# 1-Holberton_Child_Top.net
KiCad netlist of a schematic drawn in Altium Designer
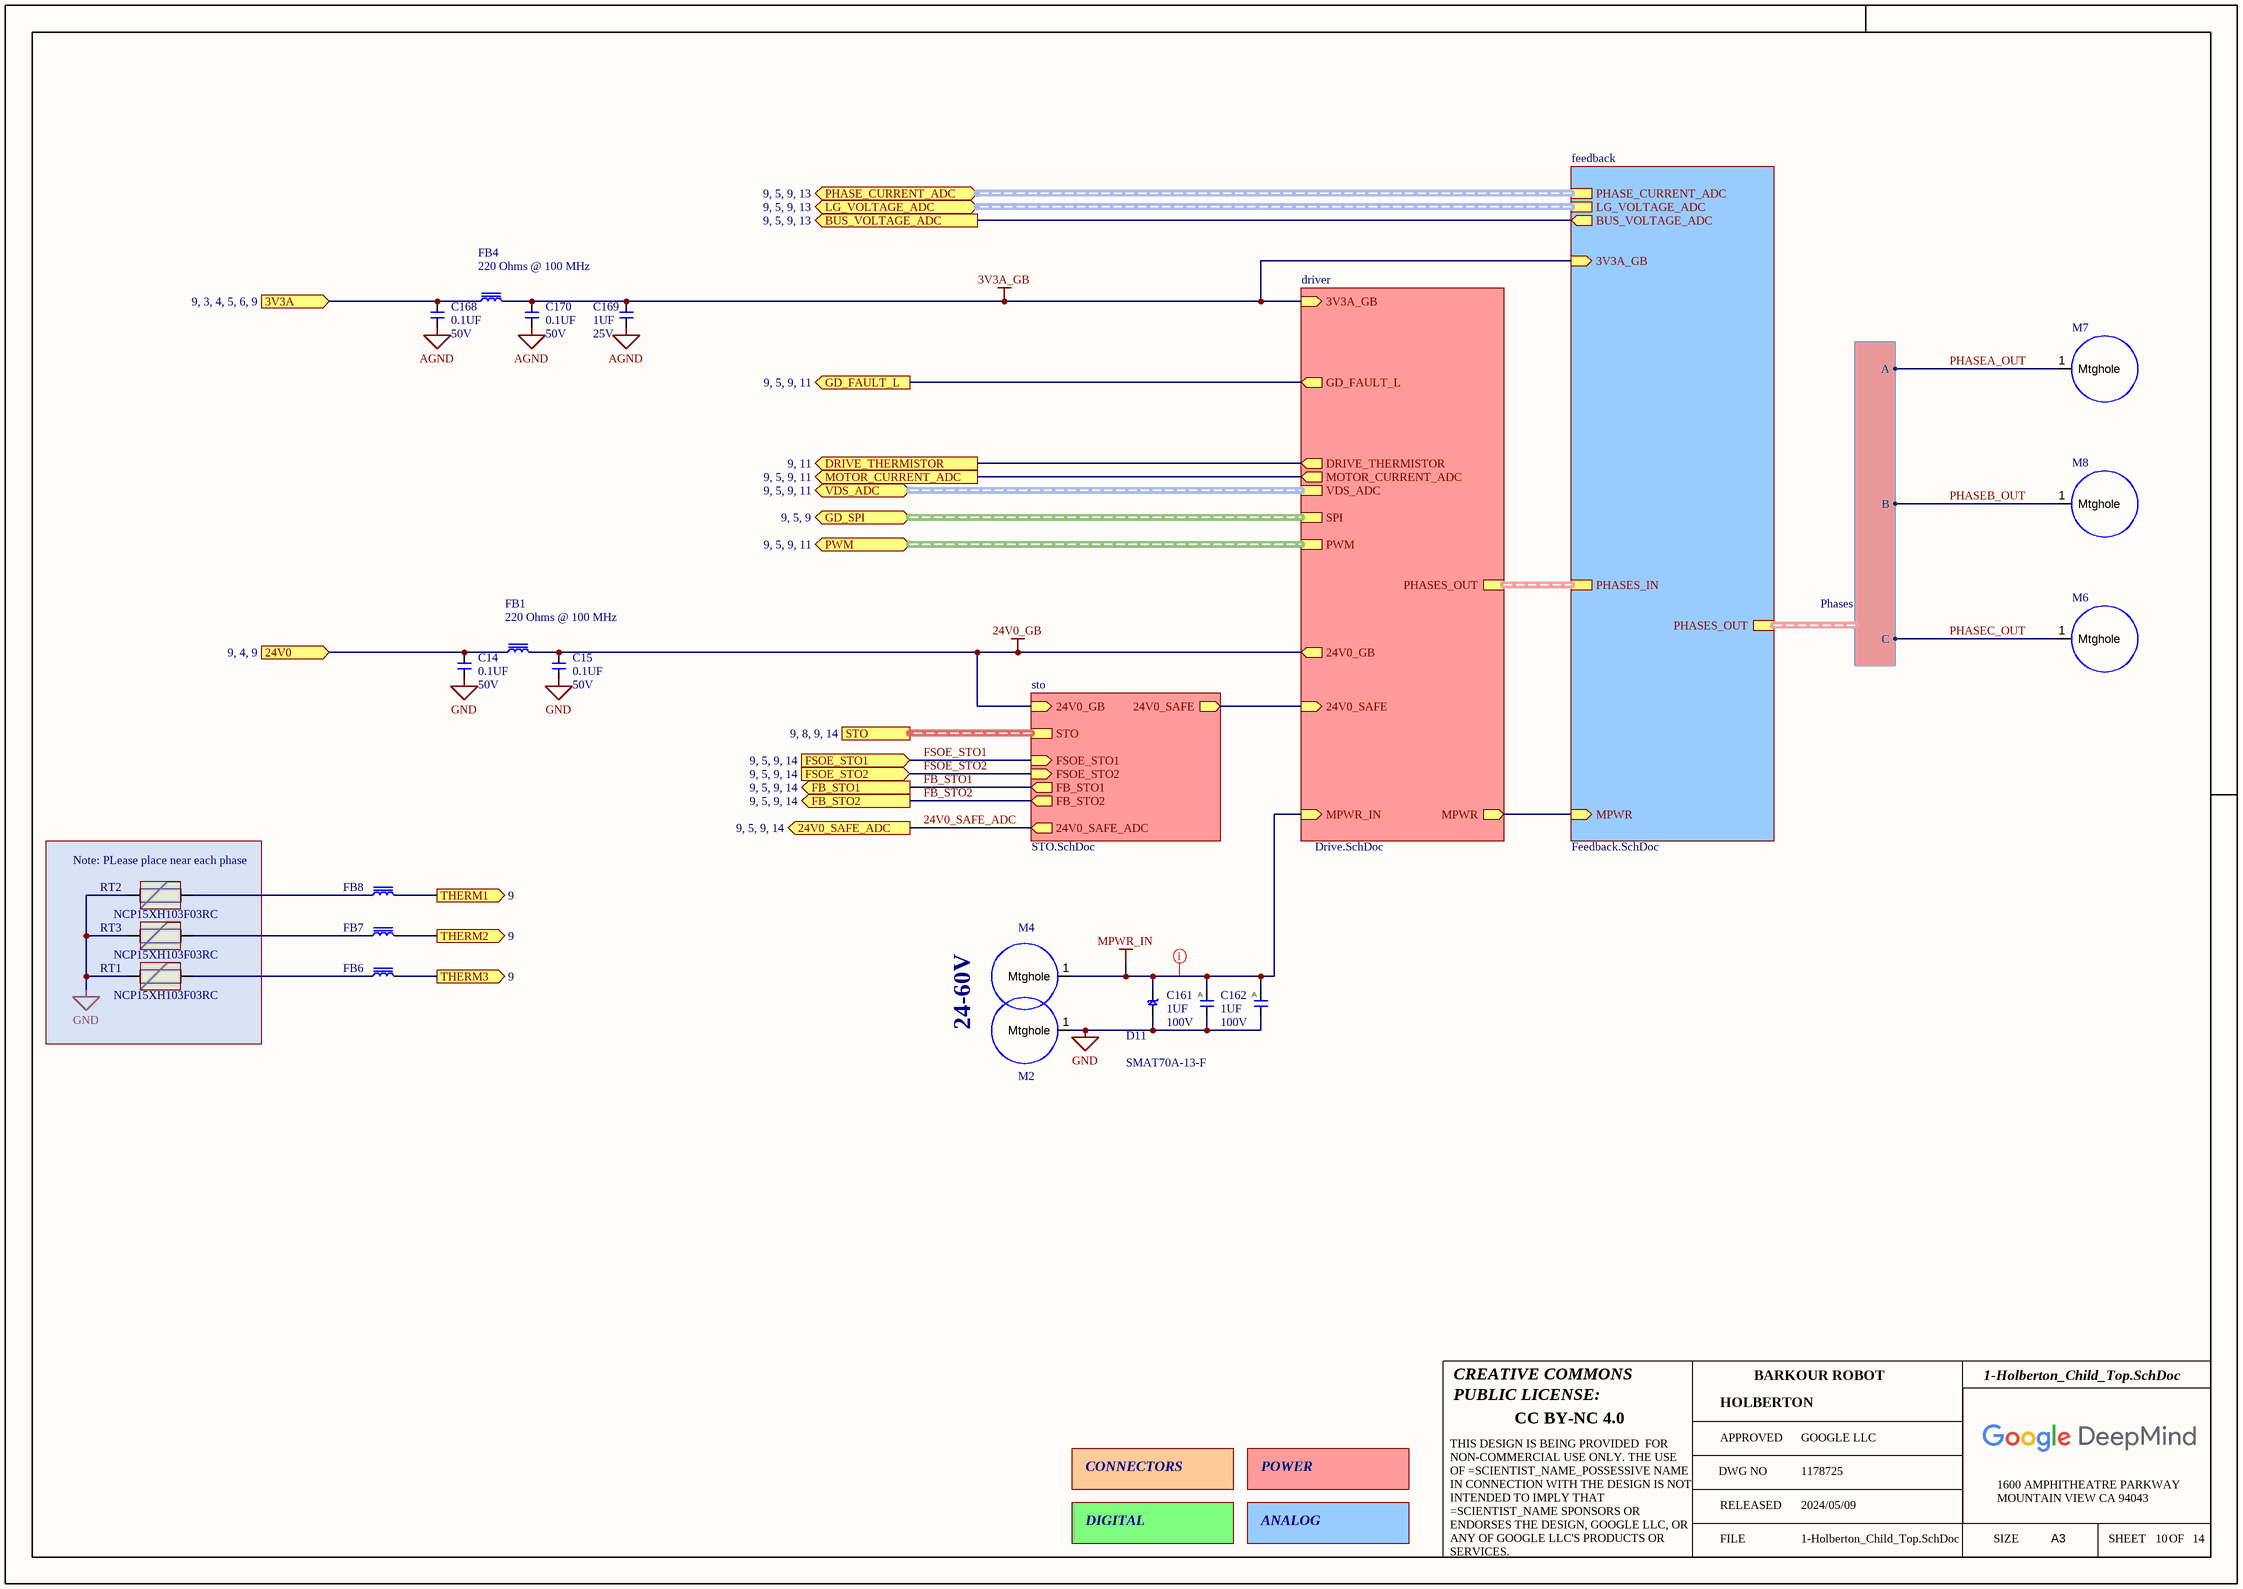
[diagram p0: 1-Holberton_Child_Top.SchDoc]

(export (version "E")
  (design (tool "Eeschema 10.0.6"))
  (components
    (comp (ref "C14")
      (value "0.1UF")
      (footprint "C0402")
      (description "CAP, CER, X5R, 0.1uF, 10%, 50V, 0402, 0.55mm")
      (fields
        (field (name "MFG") "YAGEO")
        (field (name "VOLTAGE") "50V")
        (field (name "Comment") "__Template_Cap")
      )
      (libsource (lib "AltiumReleaseLibDB") (part "__Template_Cap"))
    )
    (comp (ref "C15")
      (value "0.1UF")
      (footprint "C0402")
      (description "CAP, CER, X5R, 0.1uF, 10%, 50V, 0402, 0.55mm")
      (fields
        (field (name "MFG") "YAGEO")
        (field (name "VOLTAGE") "50V")
        (field (name "Comment") "__Template_Cap")
      )
      (libsource (lib "AltiumReleaseLibDB") (part "__Template_Cap"))
    )
    (comp (ref "C161")
      (value "1UF")
      (footprint "C0805")
      (description "CAP, CER, X7S, 1uF, 20%, 100V, 0805")
      (fields
        (field (name "MFG") "TDK")
        (field (name "VOLTAGE") "100V")
        (field (name "Comment") "__Template_Cap_Auto")
      )
      (libsource (lib "AltiumReleaseLibDB") (part "__Template_Cap_Auto"))
    )
    (comp (ref "C162")
      (value "1UF")
      (footprint "C0805")
      (description "CAP, CER, X7S, 1uF, 20%, 100V, 0805")
      (fields
        (field (name "MFG") "TDK")
        (field (name "VOLTAGE") "100V")
        (field (name "Comment") "__Template_Cap_Auto")
      )
      (libsource (lib "AltiumReleaseLibDB") (part "__Template_Cap_Auto"))
    )
    (comp (ref "C168")
      (value "0.1UF")
      (footprint "C0402")
      (description "CAP, CER, X5R, 0.1uF, 10%, 50V, 0402, 0.55mm")
      (fields
        (field (name "MFG") "YAGEO")
        (field (name "VOLTAGE") "50V")
        (field (name "Comment") "__Template_Cap")
      )
      (libsource (lib "AltiumReleaseLibDB") (part "__Template_Cap"))
    )
    (comp (ref "C169")
      (value "1UF")
      (footprint "C0402")
      (description "CAP, CER, X5R, 1uF, 10%, 25V, 0402")
      (fields
        (field (name "MFG") "TDK")
        (field (name "VOLTAGE") "25V")
        (field (name "Comment") "__Template_Cap")
      )
      (libsource (lib "AltiumReleaseLibDB") (part "__Template_Cap"))
    )
    (comp (ref "C170")
      (value "0.1UF")
      (footprint "C0402")
      (description "CAP, CER, X5R, 0.1uF, 10%, 50V, 0402, 0.55mm")
      (fields
        (field (name "MFG") "YAGEO")
        (field (name "VOLTAGE") "50V")
        (field (name "Comment") "__Template_Cap")
      )
      (libsource (lib "AltiumReleaseLibDB") (part "__Template_Cap"))
    )
    (comp (ref "D11")
      (value "SMAT70A-13-F")
      (footprint "SMA_B130-13-F")
      (description "DIODE, TVS, UNI-DIR, 70VR, 100VCL, 400W, 140PF @1MHZ, SMA")
      (fields (field (name "MFG") "Diodes Incorporated") (field (name "Comment") "__Template_Diode_TVS_A/K"))
      (libsource (lib "AltiumReleaseLibDB") (part "__Template_Diode_TVS_A/K"))
    )
    (comp (ref "FB1")
      (value "220 Ohms @ 100 MHz")
      (footprint "INDC160X80X105L30N")
      (description "FERRITE BEAD 220 OHM 0603 1LN")
      (fields
        (field (name "MFG") "Laird-Signal Integrity Products")
        (field (name "Comment") "LAIRD MI0603L221R-10")
      )
      (libsource (lib "Components") (part "FB"))
    )
    (comp (ref "FB4")
      (value "220 Ohms @ 100 MHz")
      (footprint "INDC160X80X105L30N")
      (description "FERRITE BEAD 220 OHM 0603 1LN")
      (fields
        (field (name "MFG") "Laird-Signal Integrity Products")
        (field (name "Comment") "LAIRD MI0603L221R-10")
      )
      (libsource (lib "Components") (part "FB"))
    )
    (comp (ref "FB6")
      (value "LAIRD MI0603L221R-10")
      (footprint "INDC160X80X105L30N")
      (description "FERRITE BEAD 220 OHM 0603 1LN")
      (fields (field (name "MFG") "Laird-Signal Integrity Products"))
      (libsource (lib "Components") (part "FB"))
    )
    (comp (ref "FB7")
      (value "LAIRD MI0603L221R-10")
      (footprint "INDC160X80X105L30N")
      (description "FERRITE BEAD 220 OHM 0603 1LN")
      (fields (field (name "MFG") "Laird-Signal Integrity Products"))
      (libsource (lib "Components") (part "FB"))
    )
    (comp (ref "FB8")
      (value "LAIRD MI0603L221R-10")
      (footprint "INDC160X80X105L30N")
      (description "FERRITE BEAD 220 OHM 0603 1LN")
      (fields (field (name "MFG") "Laird-Signal Integrity Products"))
      (libsource (lib "Components") (part "FB"))
    )
    (comp (ref "M2")
      (value "1.7mm hole 5mm pad")
      (footprint "1.7hole5padRD")
      (libsource (lib "MiscSch1") (part "MtgHole_1"))
    )
    (comp (ref "M4")
      (value "1.7mm hole 5mm pad")
      (footprint "1.7hole5padRD")
      (libsource (lib "MiscSch1") (part "MtgHole_1"))
    )
    (comp (ref "M6")
      (value "Keystone_8737")
      (footprint "Keystone_8737")
      (description "Motor lead attachement points Keystone_8737")
      (fields (field (name "MFG") "Keystone Electronics"))
      (libsource (lib "MiscSch1") (part "MtgHole_1"))
    )
    (comp (ref "M7")
      (value "Keystone_8737")
      (footprint "Keystone_8737")
      (description "Motor lead attachement points Keystone_8737")
      (fields (field (name "MFG") "Keystone Electronics"))
      (libsource (lib "MiscSch1") (part "MtgHole_1"))
    )
    (comp (ref "M8")
      (value "Keystone_8737")
      (footprint "Keystone_8737")
      (description "Motor lead attachement points Keystone_8737")
      (fields (field (name "MFG") "Keystone Electronics"))
      (libsource (lib "MiscSch1") (part "MtgHole_1"))
    )
    (comp (ref "RT1")
      (value "__Template_Thermistor")
      (footprint "R0402")
      (description "SENSOR, THERMISTOR, NTC, 10K, 1%, 3380K, 100mW, 0402")
      (fields (field (name "MFG") "Murata Electronics") (field (name "MFG P/N") "NCP15XH103F03RC"))
      (libsource (lib "AltiumReleaseLibDB") (part "__Template_Thermistor"))
    )
    (comp (ref "RT2")
      (value "__Template_Thermistor")
      (footprint "R0402")
      (description "SENSOR, THERMISTOR, NTC, 10K, 1%, 3380K, 100mW, 0402")
      (fields (field (name "MFG") "Murata Electronics") (field (name "MFG P/N") "NCP15XH103F03RC"))
      (libsource (lib "AltiumReleaseLibDB") (part "__Template_Thermistor"))
    )
    (comp (ref "RT3")
      (value "__Template_Thermistor")
      (footprint "R0402")
      (description "SENSOR, THERMISTOR, NTC, 10K, 1%, 3380K, 100mW, 0402")
      (fields (field (name "MFG") "Murata Electronics") (field (name "MFG P/N") "NCP15XH103F03RC"))
      (libsource (lib "AltiumReleaseLibDB") (part "__Template_Thermistor"))
    )
  )
  (nets
    (net (code "3") (name "/3V3A") (class "Default")
      (node (ref "C168") (pin "1") (pintype "passive"))
      (node (ref "FB4") (pin "1") (pintype "passive"))
    )
    (net (code "4") (name "/24V0") (class "Default")
      (node (ref "C14") (pin "1") (pintype "passive"))
      (node (ref "FB1") (pin "1") (pintype "passive"))
    )
    (net (code "18") (name "/PHASEA_OUT") (class "Default")
      (node (ref "M7") (pin "1") (pinfunction "Mtghole_1") (pintype "passive"))
    )
    (net (code "19") (name "/PHASEB_OUT") (class "Default")
      (node (ref "M8") (pin "1") (pinfunction "Mtghole_1") (pintype "passive"))
    )
    (net (code "20") (name "/PHASEC_OUT") (class "Default")
      (node (ref "M6") (pin "1") (pinfunction "Mtghole_1") (pintype "passive"))
    )
    (net (code "25") (name "/THERM1") (class "Default") (node (ref "FB8") (pin "2") (pintype "passive")))
    (net (code "26") (name "/THERM2") (class "Default") (node (ref "FB7") (pin "2") (pintype "passive")))
    (net (code "27") (name "/THERM3") (class "Default") (node (ref "FB6") (pin "2") (pintype "passive")))
    (net (code "30") (name "3V3A_GB") (class "Default")
      (node (ref "C169") (pin "1") (pintype "passive"))
      (node (ref "C170") (pin "1") (pintype "passive"))
      (node (ref "FB4") (pin "2") (pintype "passive"))
    )
    (net (code "31") (name "24V0_GB") (class "Default")
      (node (ref "C15") (pin "1") (pintype "passive"))
      (node (ref "FB1") (pin "2") (pintype "passive"))
    )
    (net (code "32") (name "AGND") (class "Default")
      (node (ref "C168") (pin "2") (pintype "passive"))
      (node (ref "C169") (pin "2") (pintype "passive"))
      (node (ref "C170") (pin "2") (pintype "passive"))
    )
    (net (code "33") (name "GND") (class "Default")
      (node (ref "C14") (pin "2") (pintype "passive"))
      (node (ref "C15") (pin "2") (pintype "passive"))
      (node (ref "C161") (pin "2") (pintype "passive"))
      (node (ref "C162") (pin "2") (pintype "passive"))
      (node (ref "D11") (pin "A") (pinfunction "A_A") (pintype "passive"))
      (node (ref "M2") (pin "1") (pinfunction "Mtghole_1") (pintype "passive"))
      (node (ref "RT1") (pin "2") (pintype "passive"))
      (node (ref "RT2") (pin "2") (pintype "passive"))
      (node (ref "RT3") (pin "2") (pintype "passive"))
    )
    (net (code "34") (name "MPWR_IN") (class "Default")
      (node (ref "C161") (pin "1") (pintype "passive"))
      (node (ref "C162") (pin "1") (pintype "passive"))
      (node (ref "D11") (pin "K") (pinfunction "K_K") (pintype "passive"))
      (node (ref "M4") (pin "1") (pinfunction "Mtghole_1") (pintype "passive"))
    )
    (net (code "35") (name "Net-(FB6-Pad1)") (class "Default")
      (node (ref "FB6") (pin "1") (pintype "passive"))
      (node (ref "RT1") (pin "1") (pintype "passive"))
    )
    (net (code "36") (name "Net-(FB7-Pad1)") (class "Default")
      (node (ref "FB7") (pin "1") (pintype "passive"))
      (node (ref "RT3") (pin "1") (pintype "passive"))
    )
    (net (code "37") (name "Net-(FB8-Pad1)") (class "Default")
      (node (ref "FB8") (pin "1") (pintype "passive"))
      (node (ref "RT2") (pin "1") (pintype "passive"))
    )
  )
)
